# Flight-Mill-Controller.net
KiCad netlist of a schematic drawn in EAGLE
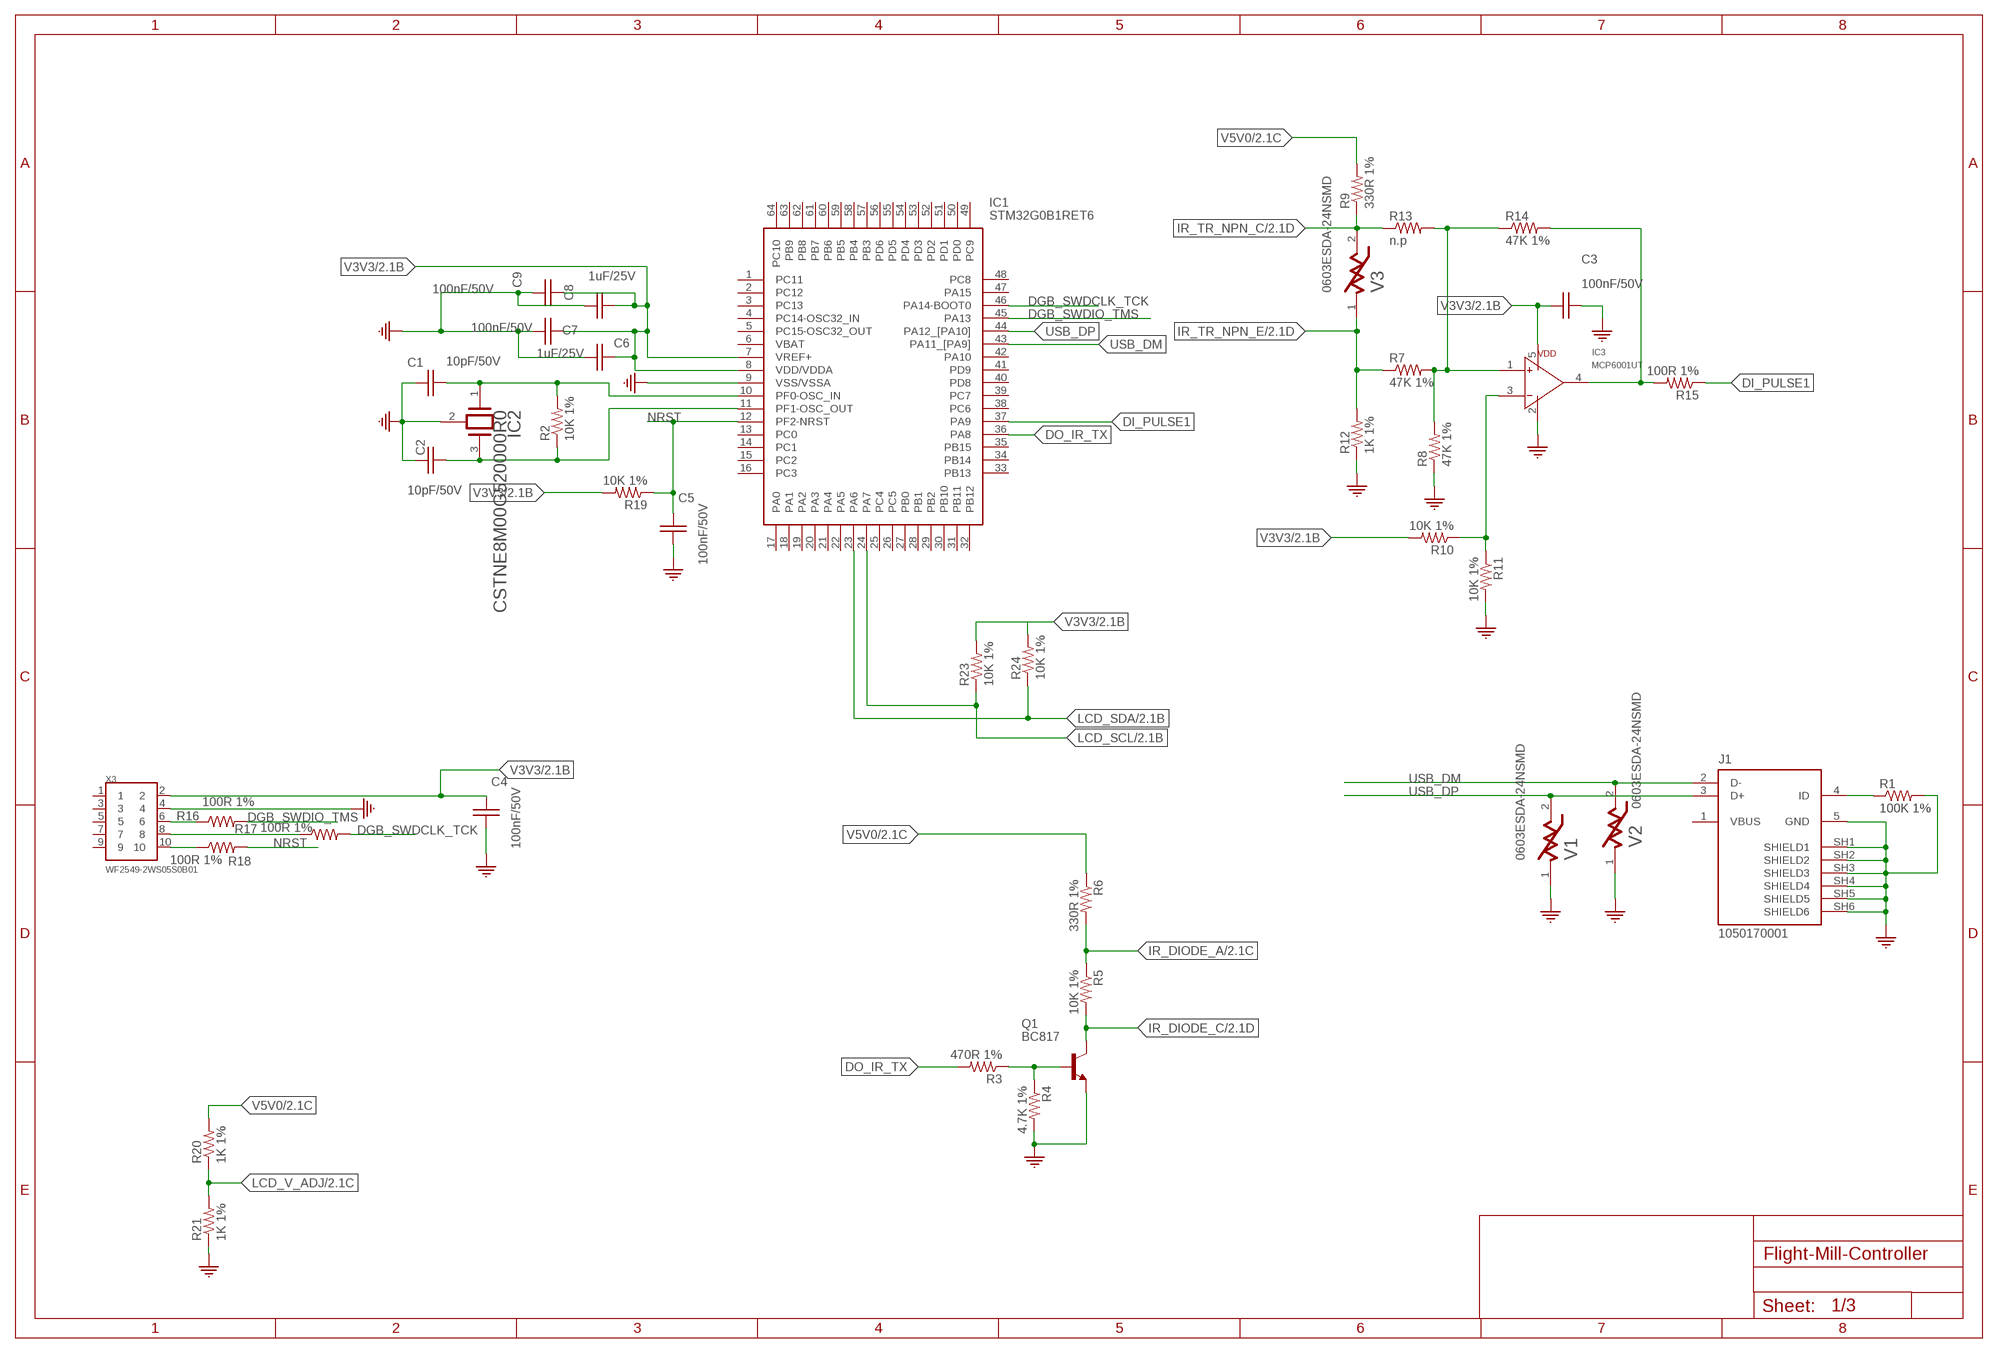
[diagram p0: schematic, sheet 1]
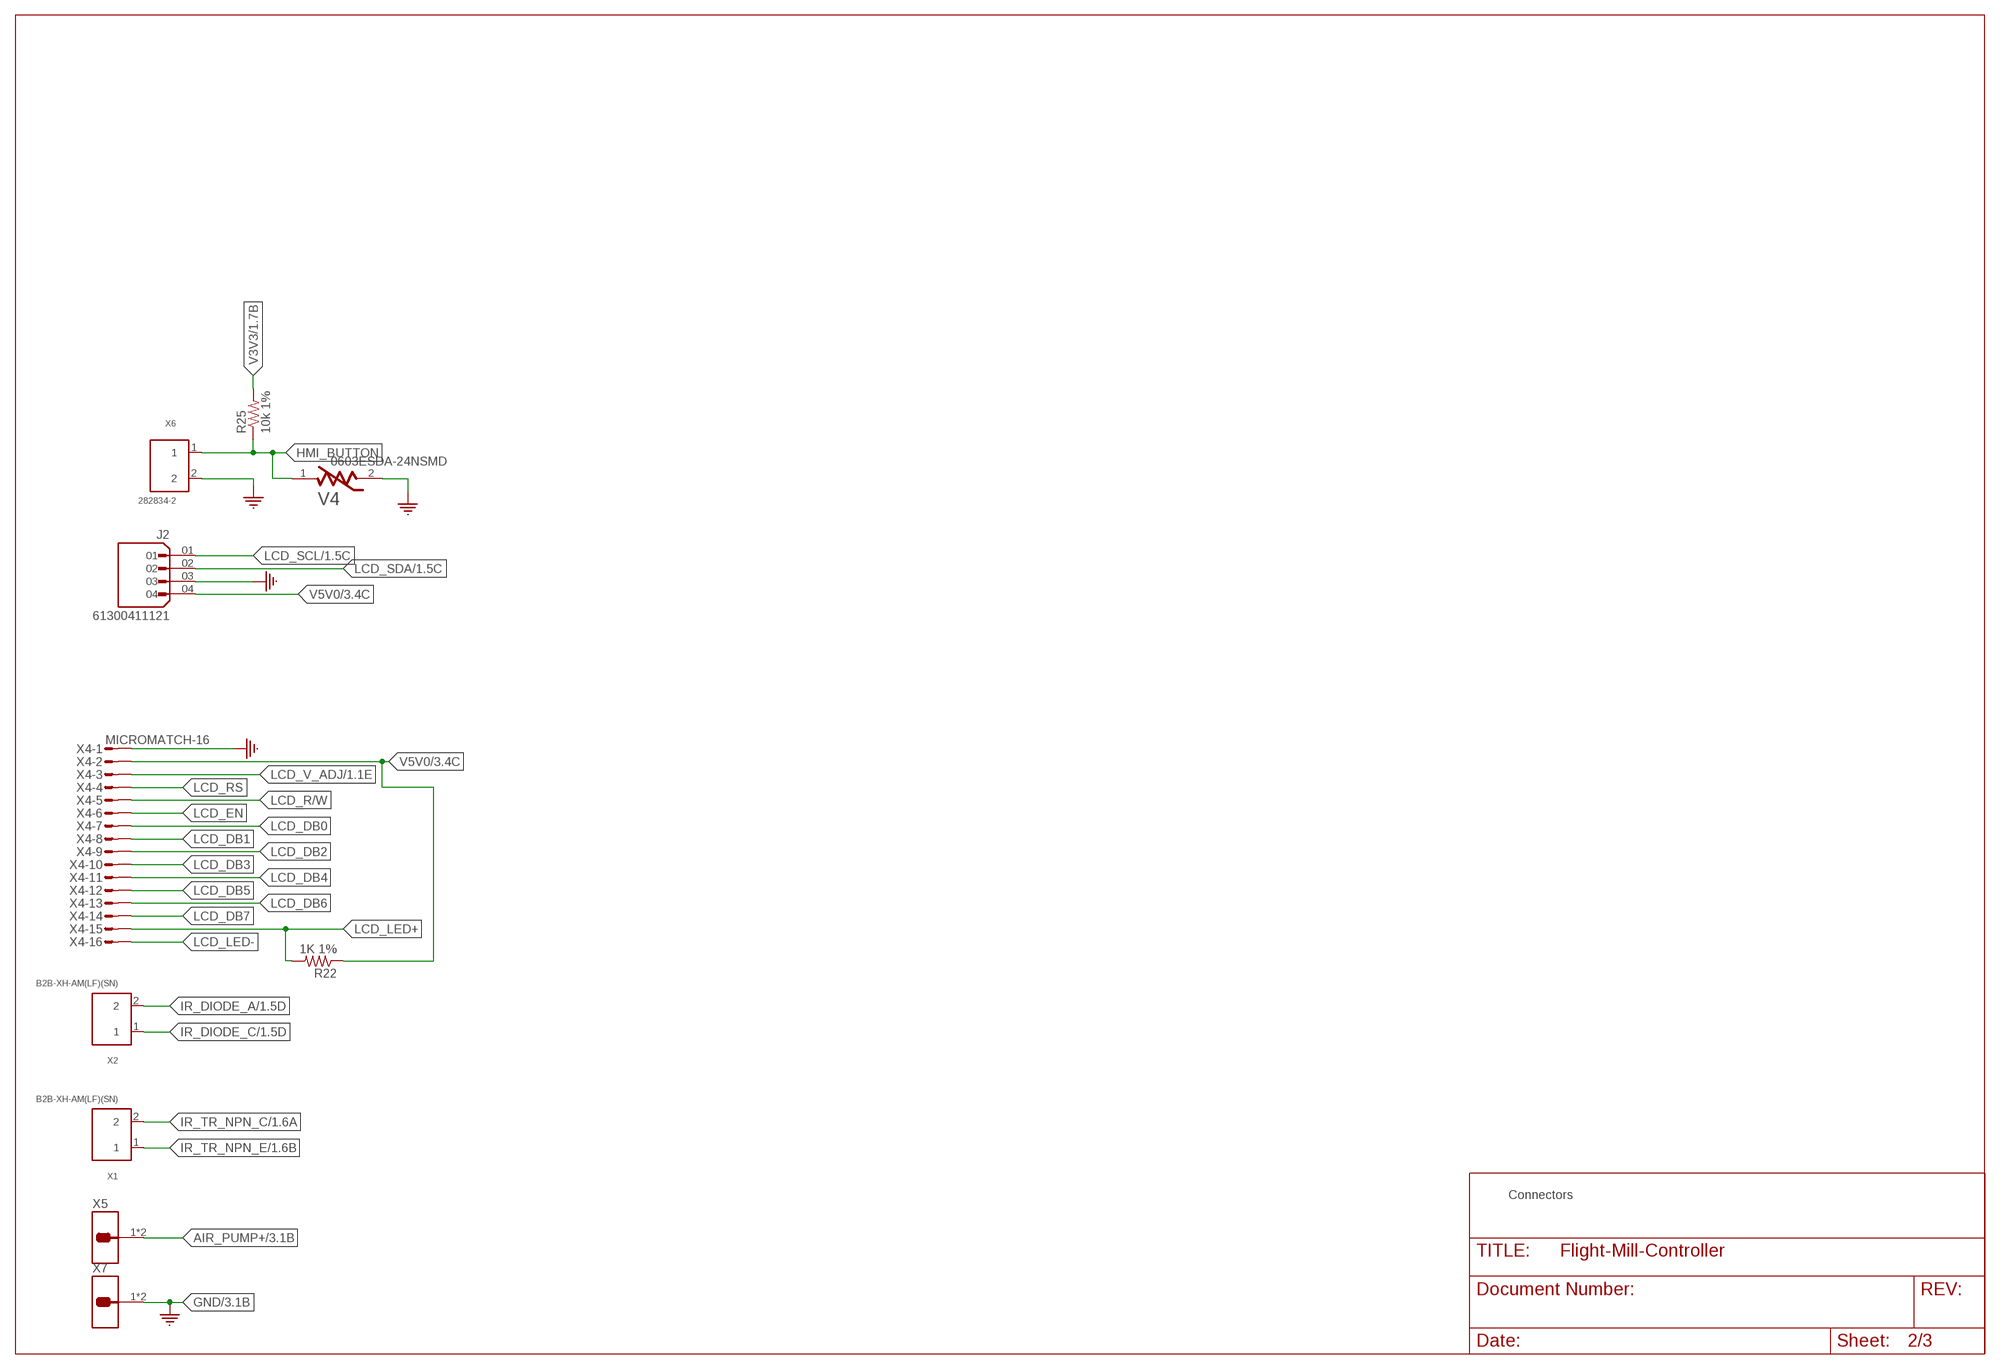
[diagram p1: schematic, sheet 2]
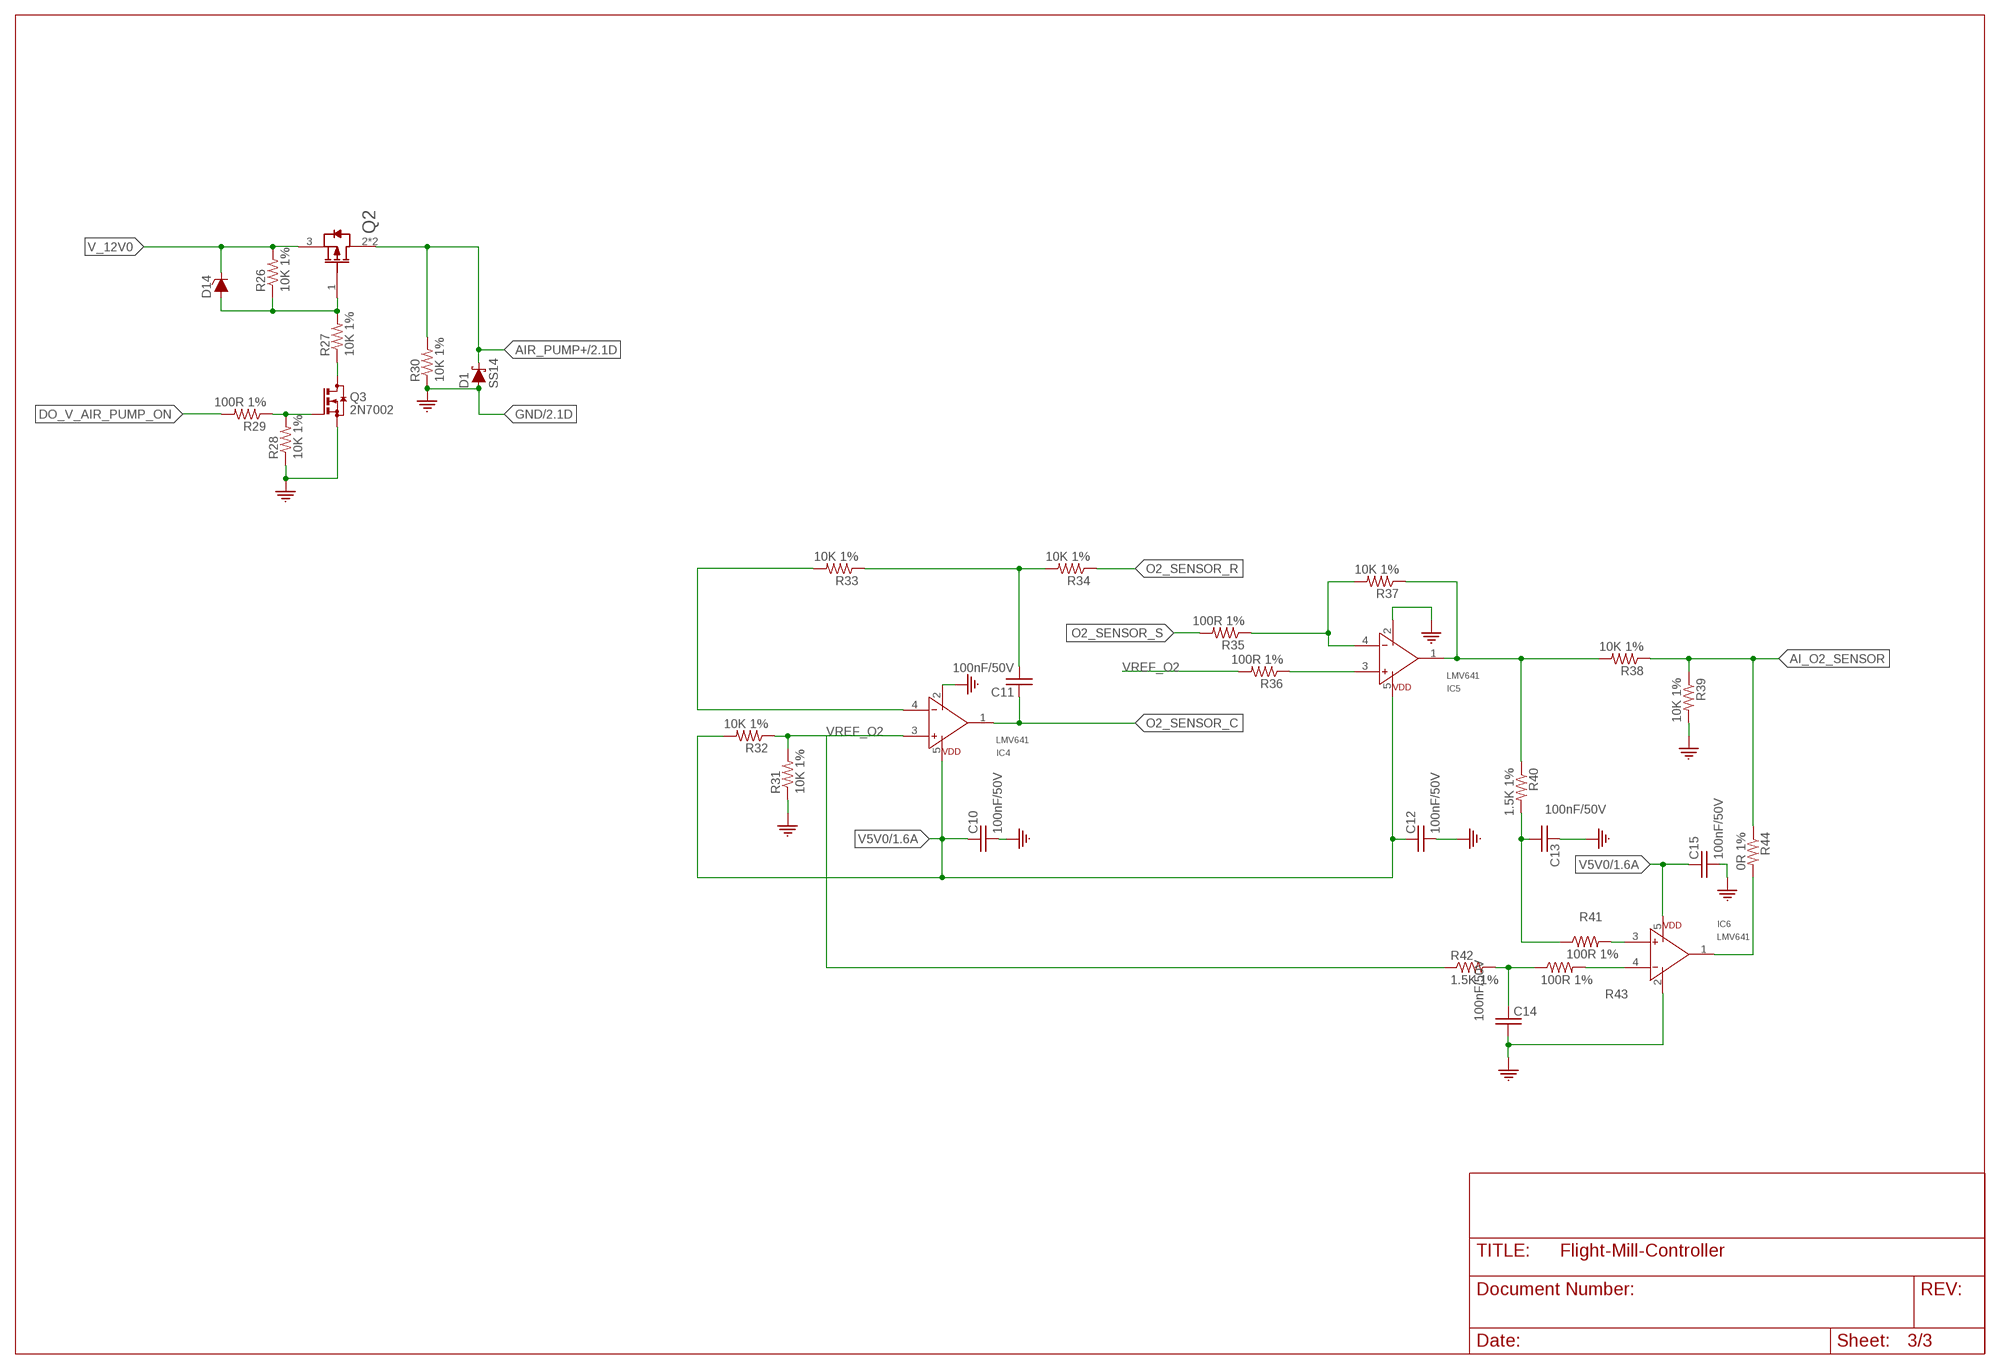
[diagram p2: schematic, sheet 3]

(export (version "E")
  (design (tool "Eeschema 10.0.6"))
  (components
    (comp (ref "C1")
      (value "10pF/50V")
      (footprint "eagle-import:EIA0603")
      (libsource (lib "eagle-import") (part "C_0603EIA0603"))
    )
    (comp (ref "C2")
      (value "10pF/50V")
      (footprint "eagle-import:EIA0603")
      (libsource (lib "eagle-import") (part "C_0603EIA0603"))
    )
    (comp (ref "C3")
      (value "100nF/50V")
      (footprint "eagle-import:EIA0603")
      (libsource (lib "eagle-import") (part "C_0603EIA0603"))
    )
    (comp (ref "C4")
      (value "100nF/50V")
      (footprint "eagle-import:EIA0603")
      (libsource (lib "eagle-import") (part "C_0603EIA0603"))
    )
    (comp (ref "C5")
      (value "100nF/50V")
      (footprint "eagle-import:EIA0603")
      (libsource (lib "eagle-import") (part "C_0603EIA0603"))
    )
    (comp (ref "C6")
      (value "1uF/25V")
      (footprint "eagle-import:EIA0603")
      (libsource (lib "eagle-import") (part "C_0603EIA0603"))
    )
    (comp (ref "C7")
      (value "100nF/50V")
      (footprint "eagle-import:EIA0603")
      (libsource (lib "eagle-import") (part "C_0603EIA0603"))
    )
    (comp (ref "C8")
      (value "1uF/25V")
      (footprint "eagle-import:EIA0603")
      (libsource (lib "eagle-import") (part "C_0603EIA0603"))
    )
    (comp (ref "C9")
      (value "100nF/50V")
      (footprint "eagle-import:EIA0603")
      (libsource (lib "eagle-import") (part "C_0603EIA0603"))
    )
    (comp (ref "IC1")
      (value "STM32G0B1RET6")
      (footprint "eagle-import:QFP50P1200X1200X160-64N")
      (fields (field (name "MOUSER_PART_NUMBER") "511-STM32G0B1RET6"))
      (libsource (lib "eagle-import") (part "STM32G0B1RET6"))
    )
    (comp (ref "IC2")
      (value "CSTNE8M00G520000R0")
      (footprint "eagle-import:CSTNE8M00G520000R0")
      (fields (field (name "MFR") "Murata"))
      (libsource (lib "eagle-import") (part "CSTNE8M00G520000R0"))
    )
    (comp (ref "IC3")
      (value "MCP6001UT")
      (footprint "eagle-import:SOT-23-5")
      (libsource (lib "eagle-import") (part "MCP6001UT"))
    )
    (comp (ref "J1")
      (value "1050170001")
      (footprint "eagle-import:MOLEX_1050170001")
      (fields (field (name "MF") "Molex"))
      (libsource (lib "eagle-import") (part "1050170001"))
    )
    (comp (ref "Q1")
      (value "BC817")
      (footprint "eagle-import:SOT23")
      (fields (field (name "MFR") "NXP"))
      (libsource (lib "eagle-import") (part "BC817"))
    )
    (comp (ref "R1")
      (value "100K 1%")
      (footprint "eagle-import:EIA0603")
      (libsource (lib "eagle-import") (part "Labops_Lib_AH_R_0603"))
    )
    (comp (ref "R2")
      (value "10K 1%")
      (footprint "eagle-import:EIA0603")
      (libsource (lib "eagle-import") (part "Labops_Lib_AH_R_0603"))
    )
    (comp (ref "R3")
      (value "470R 1%")
      (footprint "eagle-import:EIA0603")
      (libsource (lib "eagle-import") (part "Labops_Lib_AH_R_0603"))
    )
    (comp (ref "R4")
      (value "4.7K 1%")
      (footprint "eagle-import:EIA0603")
      (libsource (lib "eagle-import") (part "Labops_Lib_AH_R_0603"))
    )
    (comp (ref "R5")
      (value "10K 1%")
      (footprint "eagle-import:EIA0603")
      (libsource (lib "eagle-import") (part "Labops_Lib_AH_R_0603"))
    )
    (comp (ref "R6")
      (value "330R 1%")
      (footprint "eagle-import:EIA0603")
      (libsource (lib "eagle-import") (part "Labops_Lib_AH_R_0603"))
    )
    (comp (ref "R7")
      (value "47K 1%")
      (footprint "eagle-import:EIA0603")
      (libsource (lib "eagle-import") (part "Labops_Lib_AH_R_0603"))
    )
    (comp (ref "R8")
      (value "47K 1%")
      (footprint "eagle-import:EIA0603")
      (libsource (lib "eagle-import") (part "Labops_Lib_AH_R_0603"))
    )
    (comp (ref "R9")
      (value "330R 1%")
      (footprint "eagle-import:EIA0603")
      (libsource (lib "eagle-import") (part "Labops_Lib_AH_R_0603"))
    )
    (comp (ref "R10")
      (value "10K 1%")
      (footprint "eagle-import:EIA0603")
      (libsource (lib "eagle-import") (part "Labops_Lib_AH_R_0603"))
    )
    (comp (ref "R11")
      (value "10K 1%")
      (footprint "eagle-import:EIA0603")
      (libsource (lib "eagle-import") (part "Labops_Lib_AH_R_0603"))
    )
    (comp (ref "R12")
      (value "1K 1%")
      (footprint "eagle-import:EIA0603")
      (libsource (lib "eagle-import") (part "Labops_Lib_AH_R_0603"))
    )
    (comp (ref "R13")
      (value "n.p")
      (footprint "eagle-import:EIA0603")
      (libsource (lib "eagle-import") (part "Labops_Lib_AH_R_0603"))
    )
    (comp (ref "R14")
      (value "47K 1%")
      (footprint "eagle-import:EIA0603")
      (libsource (lib "eagle-import") (part "Labops_Lib_AH_R_0603"))
    )
    (comp (ref "R15")
      (value "100R 1%")
      (footprint "eagle-import:EIA0603")
      (libsource (lib "eagle-import") (part "Labops_Lib_AH_R_0603"))
    )
    (comp (ref "R16")
      (value "100R 1%")
      (footprint "eagle-import:EIA0603")
      (libsource (lib "eagle-import") (part "Labops_Lib_AH_R_0603"))
    )
    (comp (ref "R17")
      (value "100R 1%")
      (footprint "eagle-import:EIA0603")
      (libsource (lib "eagle-import") (part "Labops_Lib_AH_R_0603"))
    )
    (comp (ref "R18")
      (value "100R 1%")
      (footprint "eagle-import:EIA0603")
      (libsource (lib "eagle-import") (part "Labops_Lib_AH_R_0603"))
    )
    (comp (ref "R19")
      (value "10K 1%")
      (footprint "eagle-import:EIA0603")
      (libsource (lib "eagle-import") (part "Labops_Lib_AH_R_0603"))
    )
    (comp (ref "R20")
      (value "1K 1%")
      (footprint "eagle-import:EIA0603")
      (libsource (lib "eagle-import") (part "Labops_Lib_AH_R_0603"))
    )
    (comp (ref "R21")
      (value "1K 1%")
      (footprint "eagle-import:EIA0603")
      (libsource (lib "eagle-import") (part "Labops_Lib_AH_R_0603"))
    )
    (comp (ref "R23")
      (value "10K 1%")
      (footprint "eagle-import:EIA0603")
      (libsource (lib "eagle-import") (part "Labops_Lib_AH_R_0603"))
    )
    (comp (ref "R24")
      (value "10K 1%")
      (footprint "eagle-import:EIA0603")
      (libsource (lib "eagle-import") (part "Labops_Lib_AH_R_0603"))
    )
    (comp (ref "V1")
      (value "0603ESDA-24NSMD")
      (footprint "eagle-import:EIA0603")
      (fields (field (name "MFR") "Bourns"))
      (libsource (lib "eagle-import") (part "0603ESDA-24NSMD"))
    )
    (comp (ref "V2")
      (value "0603ESDA-24NSMD")
      (footprint "eagle-import:EIA0603")
      (fields (field (name "MFR") "Bourns"))
      (libsource (lib "eagle-import") (part "0603ESDA-24NSMD"))
    )
    (comp (ref "V3")
      (value "0603ESDA-24NSMD")
      (footprint "eagle-import:EIA0603")
      (fields (field (name "MFR") "Bourns"))
      (libsource (lib "eagle-import") (part "0603ESDA-24NSMD"))
    )
    (comp (ref "X3")
      (value "WF2549-2WS05S0B01")
      (footprint "eagle-import:X10_100MIL_2XROW_VERT")
      (fields (field (name "MFR") "WCON"))
      (libsource (lib "eagle-import") (part "WF2549-2WS05S0B01"))
    )
    (comp (ref "J2")
      (value "61300411121")
      (footprint "eagle-import:X04_100MIL_1ROW")
      (fields (field (name "MFR") "Wurth Electronics"))
      (libsource (lib "eagle-import") (part "61300411121"))
    )
    (comp (ref "R22")
      (value "1K 1%")
      (footprint "eagle-import:EIA0603")
      (libsource (lib "eagle-import") (part "Labops_Lib_AH_R_0603"))
    )
    (comp (ref "R25")
      (value "10k 1%")
      (footprint "eagle-import:EIA0603")
      (libsource (lib "eagle-import") (part "Labops_Lib_AH_R_0603"))
    )
    (comp (ref "V4")
      (value "0603ESDA-24NSMD")
      (footprint "eagle-import:EIA0603")
      (fields (field (name "MFR") "Bourns"))
      (libsource (lib "eagle-import") (part "0603ESDA-24NSMD"))
    )
    (comp (ref "X1")
      (value "B2B-XH-AM(LF)(SN)")
      (footprint "eagle-import:B2B-XH-AM(LF)(SN)")
      (fields (field (name "MFR") "JST"))
      (libsource (lib "eagle-import") (part "B2B-XH-AM(LF)(SN)"))
    )
    (comp (ref "X2")
      (value "B2B-XH-AM(LF)(SN)")
      (footprint "eagle-import:B2B-XH-AM(LF)(SN)")
      (fields (field (name "MFR") "JST"))
      (libsource (lib "eagle-import") (part "B2B-XH-AM(LF)(SN)"))
    )
    (comp (ref "X4")
      (value "MICROMATCH-16")
      (footprint "eagle-import:MICROMATCH-16")
      (fields (field (name "MF") "FARNELL") (field (name "MPN") "8-215464-6"))
      (libsource (lib "eagle-import") (part "MICROMATCH-16"))
    )
    (comp (ref "X5")
      (value "726386-2TE_726386-2")
      (footprint "eagle-import:TE_726386-2")
      (fields
        (field (name "DIGIKEY_PART_NUMBER") "A114371-ND")
        (field (name "MF") "TE")
        (field (name "MOUSER_PART_NUMBER") "571-726386-2")
      )
      (libsource (lib "eagle-import") (part "726386-2TE_726386-2"))
    )
    (comp (ref "X6")
      (value "282834-2")
      (footprint "eagle-import:TE_282834-2_0")
      (fields (field (name "MFR") "TE"))
      (libsource (lib "eagle-import") (part "282834-2"))
    )
    (comp (ref "X7")
      (value "726386-2TE_726386-2")
      (footprint "eagle-import:TE_726386-2")
      (fields
        (field (name "DIGIKEY_PART_NUMBER") "A114371-ND")
        (field (name "MF") "TE")
        (field (name "MOUSER_PART_NUMBER") "571-726386-2")
      )
      (libsource (lib "eagle-import") (part "726386-2TE_726386-2"))
    )
    (comp (ref "C10")
      (value "100nF/50V")
      (footprint "eagle-import:EIA0603")
      (libsource (lib "eagle-import") (part "C_0603EIA0603"))
    )
    (comp (ref "C11")
      (value "100nF/50V")
      (footprint "eagle-import:EIA0603")
      (libsource (lib "eagle-import") (part "C_0603EIA0603"))
    )
    (comp (ref "C12")
      (value "100nF/50V")
      (footprint "eagle-import:EIA0603")
      (libsource (lib "eagle-import") (part "C_0603EIA0603"))
    )
    (comp (ref "C13")
      (value "100nF/50V")
      (footprint "eagle-import:EIA0603")
      (libsource (lib "eagle-import") (part "C_0603EIA0603"))
    )
    (comp (ref "C14")
      (value "100nF/50V")
      (footprint "eagle-import:EIA0603")
      (libsource (lib "eagle-import") (part "C_0603EIA0603"))
    )
    (comp (ref "C15")
      (value "100nF/50V")
      (footprint "eagle-import:EIA0603")
      (libsource (lib "eagle-import") (part "C_0603EIA0603"))
    )
    (comp (ref "D1")
      (value "SS14")
      (footprint "eagle-import:SMA")
      (fields (field (name "MFR") "MCC"))
      (libsource (lib "eagle-import") (part "SS14"))
    )
    (comp (ref "D14")
      (value "MMBZ4696-HE3-18")
      (footprint "eagle-import:SOT23-3")
      (fields (field (name "MFR") "Vishay"))
      (libsource (lib "eagle-import") (part "MMBZ4696-HE3-18"))
    )
    (comp (ref "IC4")
      (value "LMV641")
      (footprint "eagle-import:SOT-23-5")
      (fields (field (name "MFR") "Texas Instruments"))
      (libsource (lib "eagle-import") (part "LMV641"))
    )
    (comp (ref "IC5")
      (value "LMV641")
      (footprint "eagle-import:SOT-23-5")
      (fields (field (name "MFR") "Texas Instruments"))
      (libsource (lib "eagle-import") (part "LMV641"))
    )
    (comp (ref "IC6")
      (value "LMV641")
      (footprint "eagle-import:SOT-23-5")
      (fields (field (name "MFR") "Texas Instruments"))
      (libsource (lib "eagle-import") (part "LMV641"))
    )
    (comp (ref "Q2")
      (value "UT2955G-AA3-R")
      (footprint "eagle-import:SOT223")
      (fields (field (name "MFR") "UTC"))
      (libsource (lib "eagle-import") (part "UT2955G-AA3-R"))
    )
    (comp (ref "Q3")
      (value "2N7002")
      (footprint "eagle-import:SOT23")
      (fields (field (name "MFR") "Diodes, Guangdong Hotetech,NXP"))
      (libsource (lib "eagle-import") (part "2N7002"))
    )
    (comp (ref "R26")
      (value "10K 1%")
      (footprint "eagle-import:0603")
      (libsource (lib "eagle-import") (part "R_0603"))
    )
    (comp (ref "R27")
      (value "10K 1%")
      (footprint "eagle-import:0603")
      (libsource (lib "eagle-import") (part "R_0603"))
    )
    (comp (ref "R28")
      (value "10K 1%")
      (footprint "eagle-import:0603")
      (libsource (lib "eagle-import") (part "R_0603"))
    )
    (comp (ref "R29")
      (value "100R 1%")
      (footprint "eagle-import:0603")
      (libsource (lib "eagle-import") (part "R_0603"))
    )
    (comp (ref "R30")
      (value "10K 1%")
      (footprint "eagle-import:0603")
      (libsource (lib "eagle-import") (part "R_0603"))
    )
    (comp (ref "R31")
      (value "10K 1%")
      (footprint "eagle-import:0603")
      (libsource (lib "eagle-import") (part "R_0603"))
    )
    (comp (ref "R32")
      (value "10K 1%")
      (footprint "eagle-import:0603")
      (libsource (lib "eagle-import") (part "R_0603"))
    )
    (comp (ref "R33")
      (value "10K 1%")
      (footprint "eagle-import:0603")
      (libsource (lib "eagle-import") (part "R_0603"))
    )
    (comp (ref "R34")
      (value "10K 1%")
      (footprint "eagle-import:0603")
      (libsource (lib "eagle-import") (part "R_0603"))
    )
    (comp (ref "R35")
      (value "100R 1%")
      (footprint "eagle-import:0603")
      (libsource (lib "eagle-import") (part "R_0603"))
    )
    (comp (ref "R36")
      (value "100R 1%")
      (footprint "eagle-import:0603")
      (libsource (lib "eagle-import") (part "R_0603"))
    )
    (comp (ref "R37")
      (value "10K 1%")
      (footprint "eagle-import:0603")
      (libsource (lib "eagle-import") (part "R_0603"))
    )
    (comp (ref "R38")
      (value "10K 1%")
      (footprint "eagle-import:0603")
      (libsource (lib "eagle-import") (part "R_0603"))
    )
    (comp (ref "R39")
      (value "10K 1%")
      (footprint "eagle-import:0603")
      (libsource (lib "eagle-import") (part "R_0603"))
    )
    (comp (ref "R40")
      (value "1.5K 1%")
      (footprint "eagle-import:0603")
      (libsource (lib "eagle-import") (part "R_0603"))
    )
    (comp (ref "R41")
      (value "100R 1%")
      (footprint "eagle-import:0603")
      (libsource (lib "eagle-import") (part "R_0603"))
    )
    (comp (ref "R42")
      (value "1.5K 1%")
      (footprint "eagle-import:0603")
      (libsource (lib "eagle-import") (part "R_0603"))
    )
    (comp (ref "R43")
      (value "100R 1%")
      (footprint "eagle-import:0603")
      (libsource (lib "eagle-import") (part "R_0603"))
    )
    (comp (ref "R44")
      (value "0R 1%")
      (footprint "eagle-import:0603")
      (libsource (lib "eagle-import") (part "R_0603"))
    )
  )
  (nets
    (net (code "1") (name "AIR_PUMP+") (class "Default")
      (node (ref "D1") (pin "1") (pinfunction "C_1") (pintype "passive"))
      (node (ref "Q2") (pin "2") (pinfunction "DRAIN_2") (pintype "passive"))
      (node (ref "Q2") (pin "4") (pinfunction "DRAIN_4") (pintype "passive"))
      (node (ref "R30") (pin "2") (pinfunction "2_2") (pintype "passive"))
      (node (ref "X5") (pin "1") (pinfunction "1_1") (pintype "passive"))
      (node (ref "X5") (pin "1-2") (pinfunction "1_1-2") (pintype "passive"))
    )
    (net (code "2") (name "AI_O2_SENSOR") (class "Default")
      (node (ref "IC5") (pin "1") (pinfunction "OUT_1") (pintype "passive"))
      (node (ref "R37") (pin "1") (pinfunction "1_1") (pintype "passive"))
      (node (ref "R38") (pin "1") (pinfunction "1_1") (pintype "passive"))
      (node (ref "R38") (pin "2") (pinfunction "2_2") (pintype "passive"))
      (node (ref "R39") (pin "1") (pinfunction "1_1") (pintype "passive"))
      (node (ref "R40") (pin "1") (pinfunction "1_1") (pintype "passive"))
      (node (ref "R44") (pin "1") (pinfunction "1_1") (pintype "passive"))
    )
    (net (code "3") (name "DGB_SWDCLK_TCK") (class "Default")
      (node (ref "IC1") (pin "46") (pinfunction "PA14-BOOT0_46") (pintype "bidirectional"))
      (node (ref "R17") (pin "2") (pinfunction "2_2") (pintype "passive"))
    )
    (net (code "4") (name "DGB_SWDIO_TMS") (class "Default")
      (node (ref "IC1") (pin "45") (pinfunction "PA13_45") (pintype "bidirectional"))
      (node (ref "R16") (pin "2") (pinfunction "2_2") (pintype "passive"))
    )
    (net (code "5") (name "DI_PULSE1") (class "Default")
      (node (ref "IC1") (pin "37") (pinfunction "PA9_37") (pintype "bidirectional"))
      (node (ref "R15") (pin "1") (pinfunction "1_1") (pintype "passive"))
    )
    (net (code "6") (name "DO_IR_TX") (class "Default")
      (node (ref "IC1") (pin "36") (pinfunction "PA8_36") (pintype "bidirectional"))
      (node (ref "R3") (pin "2") (pinfunction "2_2") (pintype "passive"))
    )
    (net (code "7") (name "DO_V_AIR_PUMP_ON") (class "Default")
      (node (ref "R29") (pin "2") (pinfunction "2_2") (pintype "passive"))
    )
    (net (code "8") (name "GND") (class "Default")
      (node (ref "C1") (pin "1") (pinfunction "1_1") (pintype "passive"))
      (node (ref "C10") (pin "2") (pinfunction "2_2") (pintype "passive"))
      (node (ref "C12") (pin "2") (pinfunction "2_2") (pintype "passive"))
      (node (ref "C13") (pin "1") (pinfunction "1_1") (pintype "passive"))
      (node (ref "C14") (pin "2") (pinfunction "2_2") (pintype "passive"))
      (node (ref "C15") (pin "2") (pinfunction "2_2") (pintype "passive"))
      (node (ref "C2") (pin "1") (pinfunction "1_1") (pintype "passive"))
      (node (ref "C3") (pin "2") (pinfunction "2_2") (pintype "passive"))
      (node (ref "C4") (pin "1") (pinfunction "1_1") (pintype "passive"))
      (node (ref "C5") (pin "1") (pinfunction "1_1") (pintype "passive"))
      (node (ref "C6") (pin "2") (pinfunction "2_2") (pintype "passive"))
      (node (ref "C7") (pin "2") (pinfunction "2_2") (pintype "passive"))
      (node (ref "C8") (pin "2") (pinfunction "2_2") (pintype "passive"))
      (node (ref "C9") (pin "2") (pinfunction "2_2") (pintype "passive"))
      (node (ref "D1") (pin "2") (pinfunction "A_2") (pintype "passive"))
      (node (ref "IC1") (pin "9") (pinfunction "VSS/VSSA_9") (pintype "bidirectional"))
      (node (ref "IC2") (pin "2") (pinfunction "GND_2") (pintype "power_in"))
      (node (ref "IC3") (pin "2") (pinfunction "NULL_2") (pintype "passive"))
      (node (ref "IC4") (pin "2") (pinfunction "VEE_2") (pintype "passive"))
      (node (ref "IC5") (pin "2") (pinfunction "VEE_2") (pintype "passive"))
      (node (ref "IC6") (pin "2") (pinfunction "VEE_2") (pintype "passive"))
      (node (ref "J1") (pin "5") (pinfunction "GND_5") (pintype "power_in"))
      (node (ref "J1") (pin "SH1") (pinfunction "SHIELD1_SH1") (pintype "passive"))
      (node (ref "J1") (pin "SH2") (pinfunction "SHIELD2_SH2") (pintype "passive"))
      (node (ref "J1") (pin "SH3") (pinfunction "SHIELD3_SH3") (pintype "passive"))
      (node (ref "J1") (pin "SH4") (pinfunction "SHIELD4_SH4") (pintype "passive"))
      (node (ref "J1") (pin "SH5") (pinfunction "SHIELD5_SH5") (pintype "passive"))
      (node (ref "J1") (pin "SH6") (pinfunction "SHIELD6_SH6") (pintype "passive"))
      (node (ref "J2") (pin "03") (pinfunction "03_03") (pintype "passive"))
      (node (ref "Q1") (pin "2") (pinfunction "E_2") (pintype "passive"))
      (node (ref "Q3") (pin "2") (pinfunction "S_2") (pintype "passive"))
      (node (ref "R1") (pin "2") (pinfunction "2_2") (pintype "passive"))
      (node (ref "R11") (pin "2") (pinfunction "2_2") (pintype "passive"))
      (node (ref "R12") (pin "1") (pinfunction "1_1") (pintype "passive"))
      (node (ref "R21") (pin "1") (pinfunction "1_1") (pintype "passive"))
      (node (ref "R28") (pin "1") (pinfunction "1_1") (pintype "passive"))
      (node (ref "R30") (pin "1") (pinfunction "1_1") (pintype "passive"))
      (node (ref "R31") (pin "1") (pinfunction "1_1") (pintype "passive"))
      (node (ref "R39") (pin "2") (pinfunction "2_2") (pintype "passive"))
      (node (ref "R4") (pin "2") (pinfunction "2_2") (pintype "passive"))
      (node (ref "R8") (pin "1") (pinfunction "1_1") (pintype "passive"))
      (node (ref "V1") (pin "1") (pinfunction "1_1") (pintype "passive"))
      (node (ref "V2") (pin "1") (pinfunction "1_1") (pintype "passive"))
      (node (ref "V4") (pin "2") (pinfunction "2_2") (pintype "passive"))
      (node (ref "X3") (pin "4") (pinfunction "4_4") (pintype "bidirectional"))
      (node (ref "X4") (pin "1") (pinfunction "S_1") (pintype "passive"))
      (node (ref "X6") (pin "2") (pinfunction "2_2") (pintype "bidirectional"))
      (node (ref "X7") (pin "1") (pinfunction "1_1") (pintype "passive"))
      (node (ref "X7") (pin "1-2") (pinfunction "1_1-2") (pintype "passive"))
    )
    (net (code "9") (name "HMI_BUTTON") (class "Default")
      (node (ref "R25") (pin "1") (pinfunction "1_1") (pintype "passive"))
      (node (ref "V4") (pin "1") (pinfunction "1_1") (pintype "passive"))
      (node (ref "X6") (pin "1") (pinfunction "1_1") (pintype "bidirectional"))
    )
    (net (code "10") (name "IR_DIODE_A") (class "Default")
      (node (ref "R5") (pin "1") (pinfunction "1_1") (pintype "passive"))
      (node (ref "R6") (pin "2") (pinfunction "2_2") (pintype "passive"))
      (node (ref "X2") (pin "2") (pinfunction "2_2") (pintype "bidirectional"))
    )
    (net (code "11") (name "IR_DIODE_C") (class "Default")
      (node (ref "Q1") (pin "3") (pinfunction "C_3") (pintype "passive"))
      (node (ref "R5") (pin "2") (pinfunction "2_2") (pintype "passive"))
      (node (ref "X2") (pin "1") (pinfunction "1_1") (pintype "bidirectional"))
    )
    (net (code "12") (name "IR_TR_NPN_C") (class "Default")
      (node (ref "R13") (pin "1") (pinfunction "1_1") (pintype "passive"))
      (node (ref "R9") (pin "1") (pinfunction "1_1") (pintype "passive"))
      (node (ref "V3") (pin "2") (pinfunction "2_2") (pintype "passive"))
      (node (ref "X1") (pin "2") (pinfunction "2_2") (pintype "bidirectional"))
    )
    (net (code "13") (name "IR_TR_NPN_E") (class "Default")
      (node (ref "R12") (pin "2") (pinfunction "2_2") (pintype "passive"))
      (node (ref "R7") (pin "1") (pinfunction "1_1") (pintype "passive"))
      (node (ref "V3") (pin "1") (pinfunction "1_1") (pintype "passive"))
      (node (ref "X1") (pin "1") (pinfunction "1_1") (pintype "bidirectional"))
    )
    (net (code "14") (name "LCD_DB0") (class "Default")
      (node (ref "X4") (pin "7") (pinfunction "S_7") (pintype "passive"))
    )
    (net (code "15") (name "LCD_DB1") (class "Default")
      (node (ref "X4") (pin "8") (pinfunction "S_8") (pintype "passive"))
    )
    (net (code "16") (name "LCD_DB2") (class "Default")
      (node (ref "X4") (pin "9") (pinfunction "S_9") (pintype "passive"))
    )
    (net (code "17") (name "LCD_DB3") (class "Default")
      (node (ref "X4") (pin "10") (pinfunction "S_10") (pintype "passive"))
    )
    (net (code "18") (name "LCD_DB4") (class "Default")
      (node (ref "X4") (pin "11") (pinfunction "S_11") (pintype "passive"))
    )
    (net (code "19") (name "LCD_DB5") (class "Default")
      (node (ref "X4") (pin "12") (pinfunction "S_12") (pintype "passive"))
    )
    (net (code "20") (name "LCD_DB6") (class "Default")
      (node (ref "X4") (pin "13") (pinfunction "S_13") (pintype "passive"))
    )
    (net (code "21") (name "LCD_DB7") (class "Default")
      (node (ref "X4") (pin "14") (pinfunction "S_14") (pintype "passive"))
    )
    (net (code "22") (name "LCD_EN") (class "Default")
      (node (ref "X4") (pin "6") (pinfunction "S_6") (pintype "passive"))
    )
    (net (code "23") (name "LCD_LED+") (class "Default")
      (node (ref "R22") (pin "2") (pinfunction "2_2") (pintype "passive"))
      (node (ref "X4") (pin "15") (pinfunction "S_15") (pintype "passive"))
    )
    (net (code "24") (name "LCD_LED-") (class "Default")
      (node (ref "X4") (pin "16") (pinfunction "S_16") (pintype "passive"))
    )
    (net (code "25") (name "LCD_RS") (class "Default")
      (node (ref "X4") (pin "4") (pinfunction "S_4") (pintype "passive"))
    )
    (net (code "26") (name "LCD_R{slash}W") (class "Default")
      (node (ref "X4") (pin "5") (pinfunction "S_5") (pintype "passive"))
    )
    (net (code "27") (name "LCD_SCL") (class "Default")
      (node (ref "IC1") (pin "24") (pinfunction "PA7_24") (pintype "bidirectional"))
      (node (ref "J2") (pin "01") (pinfunction "01_01") (pintype "passive"))
      (node (ref "R23") (pin "1") (pinfunction "1_1") (pintype "passive"))
    )
    (net (code "28") (name "LCD_SDA") (class "Default")
      (node (ref "IC1") (pin "23") (pinfunction "PA6_23") (pintype "bidirectional"))
      (node (ref "J2") (pin "02") (pinfunction "02_02") (pintype "passive"))
      (node (ref "R24") (pin "1") (pinfunction "1_1") (pintype "passive"))
    )
    (net (code "29") (name "LCD_V_ADJ") (class "Default")
      (node (ref "R20") (pin "1") (pinfunction "1_1") (pintype "passive"))
      (node (ref "R21") (pin "2") (pinfunction "2_2") (pintype "passive"))
      (node (ref "X4") (pin "3") (pinfunction "S_3") (pintype "passive"))
    )
    (net (code "30") (name "NRST") (class "Default")
      (node (ref "C5") (pin "2") (pinfunction "2_2") (pintype "passive"))
      (node (ref "IC1") (pin "12") (pinfunction "PF2-NRST_12") (pintype "bidirectional"))
      (node (ref "R18") (pin "2") (pinfunction "2_2") (pintype "passive"))
      (node (ref "R19") (pin "1") (pinfunction "1_1") (pintype "passive"))
    )
    (net (code "31") (name "Net-(C11-Pad2)") (class "Default")
      (node (ref "C11") (pin "2") (pinfunction "2_2") (pintype "passive"))
      (node (ref "R33") (pin "1") (pinfunction "1_1") (pintype "passive"))
      (node (ref "R34") (pin "2") (pinfunction "2_2") (pintype "passive"))
    )
    (net (code "32") (name "Net-(C13-Pad2)") (class "Default")
      (node (ref "C13") (pin "2") (pinfunction "2_2") (pintype "passive"))
      (node (ref "R40") (pin "2") (pinfunction "2_2") (pintype "passive"))
      (node (ref "R41") (pin "1") (pinfunction "1_1") (pintype "passive"))
    )
    (net (code "33") (name "Net-(C14-Pad1)") (class "Default")
      (node (ref "C14") (pin "1") (pinfunction "1_1") (pintype "passive"))
      (node (ref "R42") (pin "2") (pinfunction "2_2") (pintype "passive"))
      (node (ref "R43") (pin "1") (pinfunction "1_1") (pintype "passive"))
    )
    (net (code "34") (name "Net-(D14-A)") (class "Default")
      (node (ref "D14") (pin "1") (pinfunction "A_1") (pintype "passive"))
      (node (ref "Q2") (pin "1") (pinfunction "GATE_1") (pintype "passive"))
      (node (ref "R26") (pin "1") (pinfunction "1_1") (pintype "passive"))
      (node (ref "R27") (pin "2") (pinfunction "2_2") (pintype "passive"))
    )
    (net (code "35") (name "Net-(IC1-PF0-OSC_IN)") (class "Default")
      (node (ref "C1") (pin "2") (pinfunction "2_2") (pintype "passive"))
      (node (ref "IC1") (pin "10") (pinfunction "PF0-OSC_IN_10") (pintype "bidirectional"))
      (node (ref "IC2") (pin "1") (pinfunction "INPUT_1") (pintype "passive"))
      (node (ref "R2") (pin "2") (pinfunction "2_2") (pintype "passive"))
    )
    (net (code "36") (name "Net-(IC1-PF1-OSC_OUT)") (class "Default")
      (node (ref "C2") (pin "2") (pinfunction "2_2") (pintype "passive"))
      (node (ref "IC1") (pin "11") (pinfunction "PF1-OSC_OUT_11") (pintype "bidirectional"))
      (node (ref "IC2") (pin "3") (pinfunction "OUTPUT_3") (pintype "passive"))
      (node (ref "R2") (pin "1") (pinfunction "1_1") (pintype "passive"))
    )
    (net (code "37") (name "Net-(IC3-NULL-Pad1)") (class "Default")
      (node (ref "IC3") (pin "1") (pinfunction "NULL_1") (pintype "passive"))
      (node (ref "R13") (pin "2") (pinfunction "2_2") (pintype "passive"))
      (node (ref "R14") (pin "1") (pinfunction "1_1") (pintype "passive"))
      (node (ref "R7") (pin "2") (pinfunction "2_2") (pintype "passive"))
      (node (ref "R8") (pin "2") (pinfunction "2_2") (pintype "passive"))
    )
    (net (code "38") (name "Net-(IC3-NULL-Pad3)") (class "Default")
      (node (ref "IC3") (pin "3") (pinfunction "NULL_3") (pintype "passive"))
      (node (ref "R10") (pin "1") (pinfunction "1_1") (pintype "passive"))
      (node (ref "R11") (pin "1") (pinfunction "1_1") (pintype "passive"))
    )
    (net (code "39") (name "Net-(IC3-NULL-Pad4)") (class "Default")
      (node (ref "IC3") (pin "4") (pinfunction "NULL_4") (pintype "passive"))
      (node (ref "R14") (pin "2") (pinfunction "2_2") (pintype "passive"))
      (node (ref "R15") (pin "2") (pinfunction "2_2") (pintype "passive"))
    )
    (net (code "40") (name "Net-(IC4-IN-)") (class "Default")
      (node (ref "IC4") (pin "4") (pinfunction "IN-_4") (pintype "passive"))
      (node (ref "R33") (pin "2") (pinfunction "2_2") (pintype "passive"))
    )
    (net (code "41") (name "Net-(IC5-IN+)") (class "Default")
      (node (ref "IC5") (pin "3") (pinfunction "IN+_3") (pintype "passive"))
      (node (ref "R36") (pin "1") (pinfunction "1_1") (pintype "passive"))
    )
    (net (code "42") (name "Net-(IC5-IN-)") (class "Default")
      (node (ref "IC5") (pin "4") (pinfunction "IN-_4") (pintype "passive"))
      (node (ref "R35") (pin "1") (pinfunction "1_1") (pintype "passive"))
      (node (ref "R37") (pin "2") (pinfunction "2_2") (pintype "passive"))
    )
    (net (code "43") (name "Net-(IC6-IN+)") (class "Default")
      (node (ref "IC6") (pin "3") (pinfunction "IN+_3") (pintype "passive"))
      (node (ref "R41") (pin "2") (pinfunction "2_2") (pintype "passive"))
    )
    (net (code "44") (name "Net-(IC6-IN-)") (class "Default")
      (node (ref "IC6") (pin "4") (pinfunction "IN-_4") (pintype "passive"))
      (node (ref "R43") (pin "2") (pinfunction "2_2") (pintype "passive"))
    )
    (net (code "45") (name "Net-(IC6-OUT)") (class "Default")
      (node (ref "IC6") (pin "1") (pinfunction "OUT_1") (pintype "passive"))
      (node (ref "R44") (pin "2") (pinfunction "2_2") (pintype "passive"))
    )
    (net (code "46") (name "Net-(J1-ID)") (class "Default")
      (node (ref "J1") (pin "4") (pinfunction "ID_4") (pintype "bidirectional"))
      (node (ref "R1") (pin "1") (pinfunction "1_1") (pintype "passive"))
    )
    (net (code "47") (name "Net-(Q1-B)") (class "Default")
      (node (ref "Q1") (pin "1") (pinfunction "B_1") (pintype "passive"))
      (node (ref "R3") (pin "1") (pinfunction "1_1") (pintype "passive"))
      (node (ref "R4") (pin "1") (pinfunction "1_1") (pintype "passive"))
    )
    (net (code "48") (name "Net-(Q3-D)") (class "Default")
      (node (ref "Q3") (pin "3") (pinfunction "D_3") (pintype "passive"))
      (node (ref "R27") (pin "1") (pinfunction "1_1") (pintype "passive"))
    )
    (net (code "49") (name "Net-(Q3-G)") (class "Default")
      (node (ref "Q3") (pin "1") (pinfunction "G_1") (pintype "passive"))
      (node (ref "R28") (pin "2") (pinfunction "2_2") (pintype "passive"))
      (node (ref "R29") (pin "1") (pinfunction "1_1") (pintype "passive"))
    )
    (net (code "50") (name "Net-(R16-Pad1)") (class "Default")
      (node (ref "R16") (pin "1") (pinfunction "1_1") (pintype "passive"))
      (node (ref "X3") (pin "6") (pinfunction "6_6") (pintype "bidirectional"))
    )
    (net (code "51") (name "Net-(R17-Pad1)") (class "Default")
      (node (ref "R17") (pin "1") (pinfunction "1_1") (pintype "passive"))
      (node (ref "X3") (pin "8") (pinfunction "8_8") (pintype "bidirectional"))
    )
    (net (code "52") (name "Net-(R18-Pad1)") (class "Default")
      (node (ref "R18") (pin "1") (pinfunction "1_1") (pintype "passive"))
      (node (ref "X3") (pin "10") (pinfunction "10_10") (pintype "bidirectional"))
    )
    (net (code "53") (name "O2_SENSOR_C") (class "Default")
      (node (ref "C11") (pin "1") (pinfunction "1_1") (pintype "passive"))
      (node (ref "IC4") (pin "1") (pinfunction "OUT_1") (pintype "passive"))
    )
    (net (code "54") (name "O2_SENSOR_R") (class "Default")
      (node (ref "R34") (pin "1") (pinfunction "1_1") (pintype "passive"))
    )
    (net (code "55") (name "O2_SENSOR_S") (class "Default")
      (node (ref "R35") (pin "2") (pinfunction "2_2") (pintype "passive"))
    )
    (net (code "56") (name "USB_DM") (class "Default")
      (node (ref "IC1") (pin "43") (pinfunction "PA11_[PA9]_43") (pintype "bidirectional"))
      (node (ref "J1") (pin "2") (pinfunction "D-_2") (pintype "bidirectional"))
      (node (ref "V2") (pin "2") (pinfunction "2_2") (pintype "passive"))
    )
    (net (code "57") (name "USB_DP") (class "Default")
      (node (ref "IC1") (pin "44") (pinfunction "PA12_[PA10]_44") (pintype "bidirectional"))
      (node (ref "J1") (pin "3") (pinfunction "D+_3") (pintype "bidirectional"))
      (node (ref "V1") (pin "2") (pinfunction "2_2") (pintype "passive"))
    )
    (net (code "58") (name "V3V3") (class "Default")
      (node (ref "C3") (pin "1") (pinfunction "1_1") (pintype "passive"))
      (node (ref "C4") (pin "2") (pinfunction "2_2") (pintype "passive"))
      (node (ref "C6") (pin "1") (pinfunction "1_1") (pintype "passive"))
      (node (ref "C7") (pin "1") (pinfunction "1_1") (pintype "passive"))
      (node (ref "C8") (pin "1") (pinfunction "1_1") (pintype "passive"))
      (node (ref "C9") (pin "1") (pinfunction "1_1") (pintype "passive"))
      (node (ref "IC1") (pin "7") (pinfunction "VREF+_7") (pintype "bidirectional"))
      (node (ref "IC1") (pin "8") (pinfunction "VDD/VDDA_8") (pintype "bidirectional"))
      (node (ref "IC3") (pin "5") (pinfunction "NULL_5") (pintype "passive"))
      (node (ref "R10") (pin "2") (pinfunction "2_2") (pintype "passive"))
      (node (ref "R19") (pin "2") (pinfunction "2_2") (pintype "passive"))
      (node (ref "R23") (pin "2") (pinfunction "2_2") (pintype "passive"))
      (node (ref "R24") (pin "2") (pinfunction "2_2") (pintype "passive"))
      (node (ref "R25") (pin "2") (pinfunction "2_2") (pintype "passive"))
      (node (ref "X3") (pin "2") (pinfunction "2_2") (pintype "bidirectional"))
    )
    (net (code "59") (name "V5V0") (class "Default")
      (node (ref "C10") (pin "1") (pinfunction "1_1") (pintype "passive"))
      (node (ref "C12") (pin "1") (pinfunction "1_1") (pintype "passive"))
      (node (ref "C15") (pin "1") (pinfunction "1_1") (pintype "passive"))
      (node (ref "IC4") (pin "5") (pinfunction "VCC_5") (pintype "passive"))
      (node (ref "IC5") (pin "5") (pinfunction "VCC_5") (pintype "passive"))
      (node (ref "IC6") (pin "5") (pinfunction "VCC_5") (pintype "passive"))
      (node (ref "J2") (pin "04") (pinfunction "04_04") (pintype "passive"))
      (node (ref "R20") (pin "2") (pinfunction "2_2") (pintype "passive"))
      (node (ref "R22") (pin "1") (pinfunction "1_1") (pintype "passive"))
      (node (ref "R32") (pin "2") (pinfunction "2_2") (pintype "passive"))
      (node (ref "R6") (pin "1") (pinfunction "1_1") (pintype "passive"))
      (node (ref "R9") (pin "2") (pinfunction "2_2") (pintype "passive"))
      (node (ref "X4") (pin "2") (pinfunction "S_2") (pintype "passive"))
    )
    (net (code "60") (name "VBUS") (class "Default")
      (node (ref "J1") (pin "1") (pinfunction "VBUS_1") (pintype "power_in"))
    )
    (net (code "61") (name "VREF_O2") (class "Default")
      (node (ref "IC4") (pin "3") (pinfunction "IN+_3") (pintype "passive"))
      (node (ref "R31") (pin "2") (pinfunction "2_2") (pintype "passive"))
      (node (ref "R32") (pin "1") (pinfunction "1_1") (pintype "passive"))
      (node (ref "R36") (pin "2") (pinfunction "2_2") (pintype "passive"))
      (node (ref "R42") (pin "1") (pinfunction "1_1") (pintype "passive"))
    )
    (net (code "62") (name "V_12V0") (class "Default")
      (node (ref "D14") (pin "3") (pinfunction "C_3") (pintype "passive"))
      (node (ref "Q2") (pin "3") (pinfunction "SOURCE_3") (pintype "passive"))
      (node (ref "R26") (pin "2") (pinfunction "2_2") (pintype "passive"))
    )
    (net (code "63") (name "unconnected-(IC1-PA0-Pad17)") (class "Default")
      (node (ref "IC1") (pin "17") (pinfunction "PA0_17") (pintype "bidirectional"))
    )
    (net (code "64") (name "unconnected-(IC1-PA1-Pad18)") (class "Default")
      (node (ref "IC1") (pin "18") (pinfunction "PA1_18") (pintype "bidirectional"))
    )
    (net (code "65") (name "unconnected-(IC1-PA2-Pad19)") (class "Default")
      (node (ref "IC1") (pin "19") (pinfunction "PA2_19") (pintype "bidirectional"))
    )
    (net (code "66") (name "unconnected-(IC1-PA3-Pad20)") (class "Default")
      (node (ref "IC1") (pin "20") (pinfunction "PA3_20") (pintype "bidirectional"))
    )
    (net (code "67") (name "unconnected-(IC1-PA4-Pad21)") (class "Default")
      (node (ref "IC1") (pin "21") (pinfunction "PA4_21") (pintype "bidirectional"))
    )
    (net (code "68") (name "unconnected-(IC1-PA5-Pad22)") (class "Default")
      (node (ref "IC1") (pin "22") (pinfunction "PA5_22") (pintype "bidirectional"))
    )
    (net (code "69") (name "unconnected-(IC1-PA10-Pad42)") (class "Default")
      (node (ref "IC1") (pin "42") (pinfunction "PA10_42") (pintype "bidirectional"))
    )
    (net (code "70") (name "unconnected-(IC1-PA15-Pad47)") (class "Default")
      (node (ref "IC1") (pin "47") (pinfunction "PA15_47") (pintype "bidirectional"))
    )
    (net (code "71") (name "unconnected-(IC1-PB0-Pad27)") (class "Default")
      (node (ref "IC1") (pin "27") (pinfunction "PB0_27") (pintype "bidirectional"))
    )
    (net (code "72") (name "unconnected-(IC1-PB1-Pad28)") (class "Default")
      (node (ref "IC1") (pin "28") (pinfunction "PB1_28") (pintype "bidirectional"))
    )
    (net (code "73") (name "unconnected-(IC1-PB2-Pad29)") (class "Default")
      (node (ref "IC1") (pin "29") (pinfunction "PB2_29") (pintype "bidirectional"))
    )
    (net (code "74") (name "unconnected-(IC1-PB3-Pad57)") (class "Default")
      (node (ref "IC1") (pin "57") (pinfunction "PB3_57") (pintype "bidirectional"))
    )
    (net (code "75") (name "unconnected-(IC1-PB4-Pad58)") (class "Default")
      (node (ref "IC1") (pin "58") (pinfunction "PB4_58") (pintype "bidirectional"))
    )
    (net (code "76") (name "unconnected-(IC1-PB5-Pad59)") (class "Default")
      (node (ref "IC1") (pin "59") (pinfunction "PB5_59") (pintype "bidirectional"))
    )
    (net (code "77") (name "unconnected-(IC1-PB6-Pad60)") (class "Default")
      (node (ref "IC1") (pin "60") (pinfunction "PB6_60") (pintype "bidirectional"))
    )
    (net (code "78") (name "unconnected-(IC1-PB7-Pad61)") (class "Default")
      (node (ref "IC1") (pin "61") (pinfunction "PB7_61") (pintype "bidirectional"))
    )
    (net (code "79") (name "unconnected-(IC1-PB8-Pad62)") (class "Default")
      (node (ref "IC1") (pin "62") (pinfunction "PB8_62") (pintype "bidirectional"))
    )
    (net (code "80") (name "unconnected-(IC1-PB9-Pad63)") (class "Default")
      (node (ref "IC1") (pin "63") (pinfunction "PB9_63") (pintype "bidirectional"))
    )
    (net (code "81") (name "unconnected-(IC1-PB10-Pad30)") (class "Default")
      (node (ref "IC1") (pin "30") (pinfunction "PB10_30") (pintype "bidirectional"))
    )
    (net (code "82") (name "unconnected-(IC1-PB11-Pad31)") (class "Default")
      (node (ref "IC1") (pin "31") (pinfunction "PB11_31") (pintype "bidirectional"))
    )
    (net (code "83") (name "unconnected-(IC1-PB12-Pad32)") (class "Default")
      (node (ref "IC1") (pin "32") (pinfunction "PB12_32") (pintype "bidirectional"))
    )
    (net (code "84") (name "unconnected-(IC1-PB13-Pad33)") (class "Default")
      (node (ref "IC1") (pin "33") (pinfunction "PB13_33") (pintype "bidirectional"))
    )
    (net (code "85") (name "unconnected-(IC1-PB14-Pad34)") (class "Default")
      (node (ref "IC1") (pin "34") (pinfunction "PB14_34") (pintype "bidirectional"))
    )
    (net (code "86") (name "unconnected-(IC1-PB15-Pad35)") (class "Default")
      (node (ref "IC1") (pin "35") (pinfunction "PB15_35") (pintype "bidirectional"))
    )
    (net (code "87") (name "unconnected-(IC1-PC0-Pad13)") (class "Default")
      (node (ref "IC1") (pin "13") (pinfunction "PC0_13") (pintype "bidirectional"))
    )
    (net (code "88") (name "unconnected-(IC1-PC1-Pad14)") (class "Default")
      (node (ref "IC1") (pin "14") (pinfunction "PC1_14") (pintype "bidirectional"))
    )
    (net (code "89") (name "unconnected-(IC1-PC2-Pad15)") (class "Default")
      (node (ref "IC1") (pin "15") (pinfunction "PC2_15") (pintype "bidirectional"))
    )
    (net (code "90") (name "unconnected-(IC1-PC3-Pad16)") (class "Default")
      (node (ref "IC1") (pin "16") (pinfunction "PC3_16") (pintype "bidirectional"))
    )
    (net (code "91") (name "unconnected-(IC1-PC4-Pad25)") (class "Default")
      (node (ref "IC1") (pin "25") (pinfunction "PC4_25") (pintype "bidirectional"))
    )
    (net (code "92") (name "unconnected-(IC1-PC5-Pad26)") (class "Default")
      (node (ref "IC1") (pin "26") (pinfunction "PC5_26") (pintype "bidirectional"))
    )
    (net (code "93") (name "unconnected-(IC1-PC6-Pad38)") (class "Default")
      (node (ref "IC1") (pin "38") (pinfunction "PC6_38") (pintype "bidirectional"))
    )
    (net (code "94") (name "unconnected-(IC1-PC7-Pad39)") (class "Default")
      (node (ref "IC1") (pin "39") (pinfunction "PC7_39") (pintype "bidirectional"))
    )
    (net (code "95") (name "unconnected-(IC1-PC8-Pad48)") (class "Default")
      (node (ref "IC1") (pin "48") (pinfunction "PC8_48") (pintype "bidirectional"))
    )
    (net (code "96") (name "unconnected-(IC1-PC9-Pad49)") (class "Default")
      (node (ref "IC1") (pin "49") (pinfunction "PC9_49") (pintype "bidirectional"))
    )
    (net (code "97") (name "unconnected-(IC1-PC10-Pad64)") (class "Default")
      (node (ref "IC1") (pin "64") (pinfunction "PC10_64") (pintype "bidirectional"))
    )
    (net (code "98") (name "unconnected-(IC1-PC11-Pad1)") (class "Default")
      (node (ref "IC1") (pin "1") (pinfunction "PC11_1") (pintype "bidirectional"))
    )
    (net (code "99") (name "unconnected-(IC1-PC12-Pad2)") (class "Default")
      (node (ref "IC1") (pin "2") (pinfunction "PC12_2") (pintype "bidirectional"))
    )
    (net (code "100") (name "unconnected-(IC1-PC13-Pad3)") (class "Default")
      (node (ref "IC1") (pin "3") (pinfunction "PC13_3") (pintype "bidirectional"))
    )
    (net (code "101") (name "unconnected-(IC1-PC14-OSC32_IN-Pad4)") (class "Default")
      (node (ref "IC1") (pin "4") (pinfunction "PC14-OSC32_IN_4") (pintype "bidirectional"))
    )
    (net (code "102") (name "unconnected-(IC1-PC15-OSC32_OUT-Pad5)") (class "Default")
      (node (ref "IC1") (pin "5") (pinfunction "PC15-OSC32_OUT_5") (pintype "bidirectional"))
    )
    (net (code "103") (name "unconnected-(IC1-PD0-Pad50)") (class "Default")
      (node (ref "IC1") (pin "50") (pinfunction "PD0_50") (pintype "bidirectional"))
    )
    (net (code "104") (name "unconnected-(IC1-PD1-Pad51)") (class "Default")
      (node (ref "IC1") (pin "51") (pinfunction "PD1_51") (pintype "bidirectional"))
    )
    (net (code "105") (name "unconnected-(IC1-PD2-Pad52)") (class "Default")
      (node (ref "IC1") (pin "52") (pinfunction "PD2_52") (pintype "bidirectional"))
    )
    (net (code "106") (name "unconnected-(IC1-PD3-Pad53)") (class "Default")
      (node (ref "IC1") (pin "53") (pinfunction "PD3_53") (pintype "bidirectional"))
    )
    (net (code "107") (name "unconnected-(IC1-PD4-Pad54)") (class "Default")
      (node (ref "IC1") (pin "54") (pinfunction "PD4_54") (pintype "bidirectional"))
    )
    (net (code "108") (name "unconnected-(IC1-PD5-Pad55)") (class "Default")
      (node (ref "IC1") (pin "55") (pinfunction "PD5_55") (pintype "bidirectional"))
    )
    (net (code "109") (name "unconnected-(IC1-PD6-Pad56)") (class "Default")
      (node (ref "IC1") (pin "56") (pinfunction "PD6_56") (pintype "bidirectional"))
    )
    (net (code "110") (name "unconnected-(IC1-PD8-Pad40)") (class "Default")
      (node (ref "IC1") (pin "40") (pinfunction "PD8_40") (pintype "bidirectional"))
    )
    (net (code "111") (name "unconnected-(IC1-PD9-Pad41)") (class "Default")
      (node (ref "IC1") (pin "41") (pinfunction "PD9_41") (pintype "bidirectional"))
    )
    (net (code "112") (name "unconnected-(IC1-VBAT-Pad6)") (class "Default")
      (node (ref "IC1") (pin "6") (pinfunction "VBAT_6") (pintype "bidirectional"))
    )
    (net (code "113") (name "unconnected-(X3-Pad1)") (class "Default")
      (node (ref "X3") (pin "1") (pinfunction "1_1") (pintype "bidirectional"))
    )
    (net (code "114") (name "unconnected-(X3-Pad3)") (class "Default")
      (node (ref "X3") (pin "3") (pinfunction "3_3") (pintype "bidirectional"))
    )
    (net (code "115") (name "unconnected-(X3-Pad5)") (class "Default")
      (node (ref "X3") (pin "5") (pinfunction "5_5") (pintype "bidirectional"))
    )
    (net (code "116") (name "unconnected-(X3-Pad7)") (class "Default")
      (node (ref "X3") (pin "7") (pinfunction "7_7") (pintype "bidirectional"))
    )
    (net (code "117") (name "unconnected-(X3-Pad9)") (class "Default")
      (node (ref "X3") (pin "9") (pinfunction "9_9") (pintype "bidirectional"))
    )
  )
)
